# snes_hook.net
KiCad netlist of a schematic drawn in Altium Designer
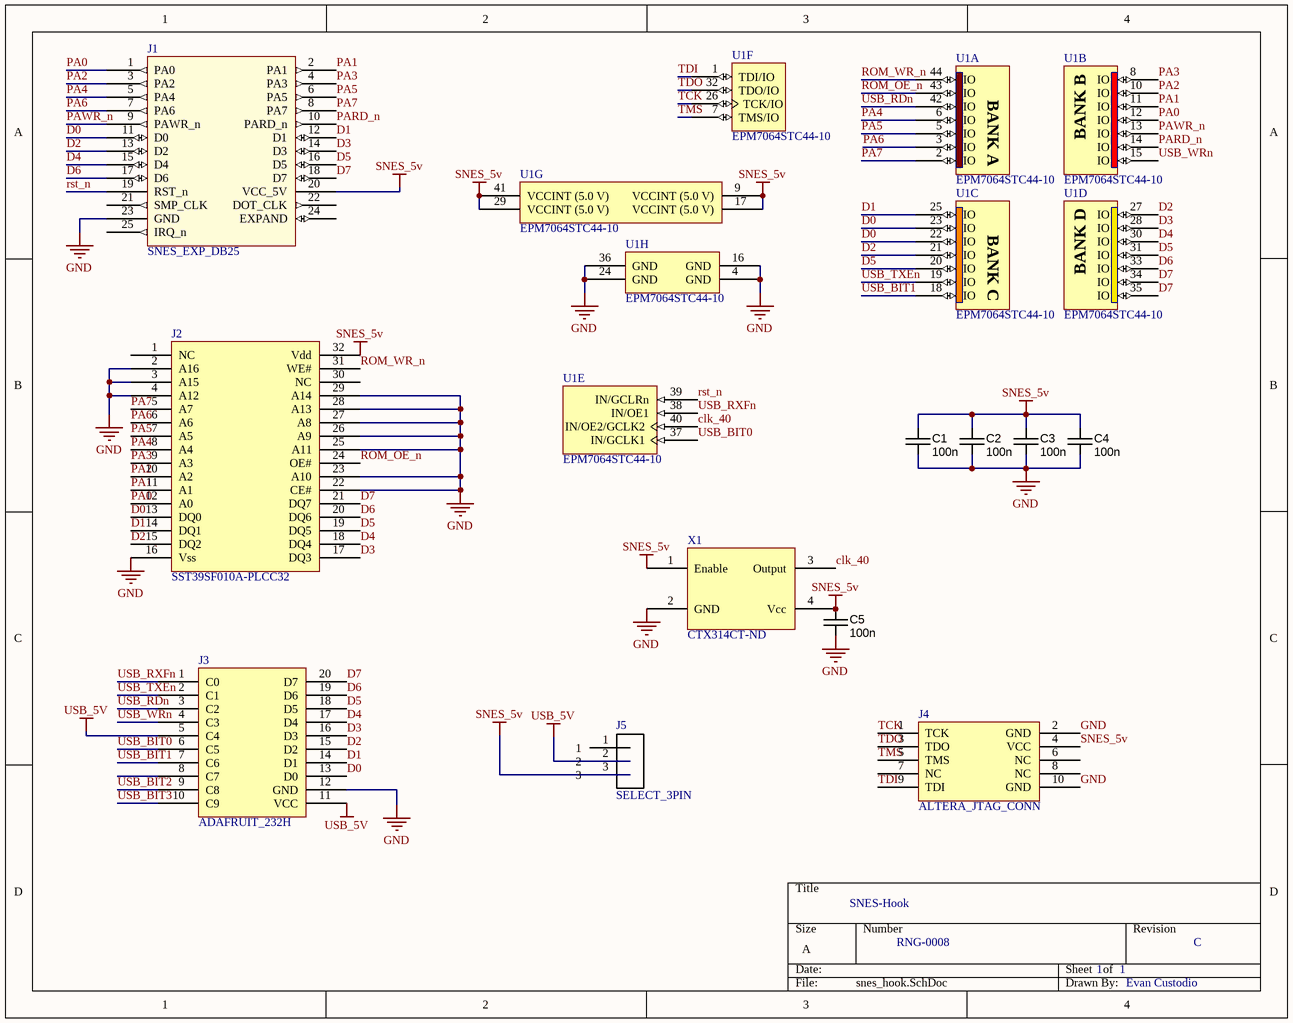
[diagram p0: snes_hook.SchDoc]

(export (version "E")
  (design (tool "Eeschema 10.0.6"))
  (components
    (comp (ref "C1")
      (value "100n")
      (footprint "CAPC1608X90N")
      (description "Capacitor SMD Cer 100nF 10% 50V X7R 0603")
      (fields (field (name "TOLERANCE") "±10%") (field (name "Comment") "approved sub OK"))
      (libsource (lib "snes_hook_parts") (part "CAPC_100n_0603_X7R_50V_10%"))
    )
    (comp (ref "C2")
      (value "100n")
      (footprint "CAPC1608X90N")
      (description "Capacitor SMD Cer 100nF 10% 50V X7R 0603")
      (fields (field (name "TOLERANCE") "±10%") (field (name "Comment") "approved sub OK"))
      (libsource (lib "snes_hook_parts") (part "CAPC_100n_0603_X7R_50V_10%"))
    )
    (comp (ref "C3")
      (value "100n")
      (footprint "CAPC1608X90N")
      (description "Capacitor SMD Cer 100nF 10% 50V X7R 0603")
      (fields (field (name "TOLERANCE") "±10%") (field (name "Comment") "approved sub OK"))
      (libsource (lib "snes_hook_parts") (part "CAPC_100n_0603_X7R_50V_10%"))
    )
    (comp (ref "C4")
      (value "100n")
      (footprint "CAPC1608X90N")
      (description "Capacitor SMD Cer 100nF 10% 50V X7R 0603")
      (fields (field (name "TOLERANCE") "±10%") (field (name "Comment") "approved sub OK"))
      (libsource (lib "snes_hook_parts") (part "CAPC_100n_0603_X7R_50V_10%"))
    )
    (comp (ref "C5")
      (value "100n")
      (footprint "CAPC1608X90N")
      (description "Capacitor SMD Cer 100nF 10% 50V X7R 0603")
      (fields (field (name "TOLERANCE") "±10%") (field (name "Comment") "approved sub OK"))
      (libsource (lib "snes_hook_parts") (part "CAPC_100n_0603_X7R_50V_10%"))
    )
    (comp (ref "J1")
      (value "SNES_EXP_DB25")
      (footprint "DB-25_RA_MPLUG")
      (libsource (lib "snes_hook_parts") (part "SNES_EXP_DB25"))
    )
    (comp (ref "J2")
      (value "SST39SF010A-PLCC32")
      (footprint "PLCC_SOCKET_7x9_32P")
      (libsource (lib "snes_hook_parts") (part "SST39SF010A-PLCC32"))
    )
    (comp (ref "J3")
      (value "ADAFRUIT_232H")
      (footprint "ADAFRUIT_232H")
      (libsource (lib "snes_hook_parts") (part "ADAFRUIT_232H"))
    )
    (comp (ref "J4")
      (value "ALTERA_JTAG_CONN")
      (footprint "JTAG_CONN")
      (libsource (lib "snes_hook_parts") (part "ALTERA_JTAG_CONN"))
    )
    (comp (ref "J5")
      (value "SELECT_3PIN")
      (footprint "HEADER_3PIN")
      (libsource (lib "snes_hook_parts") (part "SELECT_3PIN"))
    )
    (comp (ref "U1")
      (value "EPM7064STC44-10")
      (footprint "TQFP44_L")
      (fields (field (name "PUBLISHER") "Altium Limited"))
      (libsource (lib "snes_hook_parts") (part "EPM7064STC44-10"))
    )
    (comp (ref "X1")
      (value "CTX314CT-ND")
      (footprint "OSCILLATOR_7x5")
      (description "40 MHz 5v Oscillator")
      (fields
        (field (name "MANUFACTURER") "CTS-Frequency Controls")
        (field (name "MANUFACTURER PART NUMBER") "CB3-3I-40M0000")
      )
      (libsource (lib "snes_hook_parts") (part "CTX314CT-ND_40MHz"))
    )
  )
  (nets
    (net (code "1") (name "/D0") (class "Default")
      (node (ref "J1") (pin "11") (pinfunction "D0_11") (pintype "bidirectional"))
      (node (ref "J2") (pin "13") (pinfunction "DQ0_13") (pintype "passive"))
      (node (ref "J3") (pin "13") (pinfunction "D0_13") (pintype "passive"))
      (node (ref "U1") (pin "22") (pinfunction "IO_22") (pintype "bidirectional"))
      (node (ref "U1") (pin "23") (pinfunction "IO_23") (pintype "bidirectional"))
    )
    (net (code "2") (name "/D1") (class "Default")
      (node (ref "J1") (pin "12") (pinfunction "D1_12") (pintype "bidirectional"))
      (node (ref "J2") (pin "14") (pinfunction "DQ1_14") (pintype "passive"))
      (node (ref "J3") (pin "14") (pinfunction "D1_14") (pintype "passive"))
      (node (ref "U1") (pin "25") (pinfunction "IO_25") (pintype "bidirectional"))
    )
    (net (code "3") (name "/D2") (class "Default")
      (node (ref "J1") (pin "13") (pinfunction "D2_13") (pintype "bidirectional"))
      (node (ref "J2") (pin "15") (pinfunction "DQ2_15") (pintype "passive"))
      (node (ref "J3") (pin "15") (pinfunction "D2_15") (pintype "passive"))
      (node (ref "U1") (pin "21") (pinfunction "IO_21") (pintype "bidirectional"))
      (node (ref "U1") (pin "27") (pinfunction "IO_27") (pintype "bidirectional"))
    )
    (net (code "4") (name "/D3") (class "Default")
      (node (ref "J1") (pin "14") (pinfunction "D3_14") (pintype "bidirectional"))
      (node (ref "J2") (pin "17") (pinfunction "DQ3_17") (pintype "passive"))
      (node (ref "J3") (pin "16") (pinfunction "D3_16") (pintype "passive"))
      (node (ref "U1") (pin "28") (pinfunction "IO_28") (pintype "bidirectional"))
    )
    (net (code "5") (name "/D4") (class "Default")
      (node (ref "J1") (pin "15") (pinfunction "D4_15") (pintype "bidirectional"))
      (node (ref "J2") (pin "18") (pinfunction "DQ4_18") (pintype "passive"))
      (node (ref "J3") (pin "17") (pinfunction "D4_17") (pintype "passive"))
      (node (ref "U1") (pin "30") (pinfunction "IO_30") (pintype "bidirectional"))
    )
    (net (code "6") (name "/D5") (class "Default")
      (node (ref "J1") (pin "16") (pinfunction "D5_16") (pintype "bidirectional"))
      (node (ref "J2") (pin "19") (pinfunction "DQ5_19") (pintype "passive"))
      (node (ref "J3") (pin "18") (pinfunction "D5_18") (pintype "passive"))
      (node (ref "U1") (pin "20") (pinfunction "IO_20") (pintype "bidirectional"))
      (node (ref "U1") (pin "31") (pinfunction "IO_31") (pintype "bidirectional"))
    )
    (net (code "7") (name "/D6") (class "Default")
      (node (ref "J1") (pin "17") (pinfunction "D6_17") (pintype "bidirectional"))
      (node (ref "J2") (pin "20") (pinfunction "DQ6_20") (pintype "passive"))
      (node (ref "J3") (pin "19") (pinfunction "D6_19") (pintype "passive"))
      (node (ref "U1") (pin "33") (pinfunction "IO_33") (pintype "bidirectional"))
    )
    (net (code "8") (name "/D7") (class "Default")
      (node (ref "J1") (pin "18") (pinfunction "D7_18") (pintype "bidirectional"))
      (node (ref "J2") (pin "21") (pinfunction "DQ7_21") (pintype "passive"))
      (node (ref "J3") (pin "20") (pinfunction "D7_20") (pintype "passive"))
      (node (ref "U1") (pin "34") (pinfunction "IO_34") (pintype "bidirectional"))
      (node (ref "U1") (pin "35") (pinfunction "IO_35") (pintype "bidirectional"))
    )
    (net (code "9") (name "/PA0") (class "Default")
      (node (ref "J1") (pin "1") (pinfunction "PA0_1") (pintype "output"))
      (node (ref "J2") (pin "12") (pinfunction "A0_12") (pintype "passive"))
      (node (ref "U1") (pin "12") (pinfunction "IO_12") (pintype "bidirectional"))
    )
    (net (code "10") (name "/PA1") (class "Default")
      (node (ref "J1") (pin "2") (pinfunction "PA1_2") (pintype "output"))
      (node (ref "J2") (pin "11") (pinfunction "A1_11") (pintype "passive"))
      (node (ref "U1") (pin "11") (pinfunction "IO_11") (pintype "bidirectional"))
    )
    (net (code "11") (name "/PA2") (class "Default")
      (node (ref "J1") (pin "3") (pinfunction "PA2_3") (pintype "output"))
      (node (ref "J2") (pin "10") (pinfunction "A2_10") (pintype "passive"))
      (node (ref "U1") (pin "10") (pinfunction "IO_10") (pintype "bidirectional"))
    )
    (net (code "12") (name "/PA3") (class "Default")
      (node (ref "J1") (pin "4") (pinfunction "PA3_4") (pintype "output"))
      (node (ref "J2") (pin "9") (pinfunction "A3_9") (pintype "passive"))
      (node (ref "U1") (pin "8") (pinfunction "IO_8") (pintype "bidirectional"))
    )
    (net (code "13") (name "/PA4") (class "Default")
      (node (ref "J1") (pin "5") (pinfunction "PA4_5") (pintype "output"))
      (node (ref "J2") (pin "8") (pinfunction "A4_8") (pintype "passive"))
      (node (ref "U1") (pin "6") (pinfunction "IO_6") (pintype "bidirectional"))
    )
    (net (code "14") (name "/PA5") (class "Default")
      (node (ref "J1") (pin "6") (pinfunction "PA5_6") (pintype "output"))
      (node (ref "J2") (pin "7") (pinfunction "A5_7") (pintype "passive"))
      (node (ref "U1") (pin "5") (pinfunction "IO_5") (pintype "bidirectional"))
    )
    (net (code "15") (name "/PA6") (class "Default")
      (node (ref "J1") (pin "7") (pinfunction "PA6_7") (pintype "output"))
      (node (ref "J2") (pin "6") (pinfunction "A6_6") (pintype "passive"))
      (node (ref "U1") (pin "3") (pinfunction "IO_3") (pintype "bidirectional"))
    )
    (net (code "16") (name "/PA7") (class "Default")
      (node (ref "J1") (pin "8") (pinfunction "PA7_8") (pintype "output"))
      (node (ref "J2") (pin "5") (pinfunction "A7_5") (pintype "passive"))
      (node (ref "U1") (pin "2") (pinfunction "IO_2") (pintype "bidirectional"))
    )
    (net (code "17") (name "/PARD_n") (class "Default")
      (node (ref "J1") (pin "10") (pinfunction "PARD_n_10") (pintype "output"))
      (node (ref "U1") (pin "14") (pinfunction "IO_14") (pintype "bidirectional"))
    )
    (net (code "18") (name "/PAWR_n") (class "Default")
      (node (ref "J1") (pin "9") (pinfunction "PAWR_n_9") (pintype "output"))
      (node (ref "U1") (pin "13") (pinfunction "IO_13") (pintype "bidirectional"))
    )
    (net (code "19") (name "/ROM_OE_n") (class "Default")
      (node (ref "J2") (pin "24") (pinfunction "OE#_24") (pintype "passive"))
      (node (ref "U1") (pin "43") (pinfunction "IO_43") (pintype "bidirectional"))
    )
    (net (code "20") (name "/ROM_WR_n") (class "Default")
      (node (ref "J2") (pin "31") (pinfunction "WE#_31") (pintype "passive"))
      (node (ref "U1") (pin "44") (pinfunction "IO_44") (pintype "bidirectional"))
    )
    (net (code "21") (name "/TCK") (class "Default")
      (node (ref "J4") (pin "1") (pinfunction "TCK_1") (pintype "passive"))
      (node (ref "U1") (pin "26") (pinfunction "TCK/IO_26") (pintype "bidirectional"))
    )
    (net (code "22") (name "/TDI") (class "Default")
      (node (ref "J4") (pin "9") (pinfunction "TDI_9") (pintype "passive"))
      (node (ref "U1") (pin "1") (pinfunction "TDI/IO_1") (pintype "bidirectional"))
    )
    (net (code "23") (name "/TDO") (class "Default")
      (node (ref "J4") (pin "3") (pinfunction "TDO_3") (pintype "passive"))
      (node (ref "U1") (pin "32") (pinfunction "TDO/IO_32") (pintype "bidirectional"))
    )
    (net (code "24") (name "/TMS") (class "Default")
      (node (ref "J4") (pin "5") (pinfunction "TMS_5") (pintype "passive"))
      (node (ref "U1") (pin "7") (pinfunction "TMS/IO_7") (pintype "bidirectional"))
    )
    (net (code "25") (name "/USB_BIT0") (class "Default")
      (node (ref "J3") (pin "6") (pinfunction "C5_6") (pintype "passive"))
      (node (ref "U1") (pin "37") (pinfunction "IN/GCLK1_37") (pintype "input"))
    )
    (net (code "26") (name "/USB_BIT1") (class "Default")
      (node (ref "J3") (pin "7") (pinfunction "C6_7") (pintype "passive"))
      (node (ref "U1") (pin "18") (pinfunction "IO_18") (pintype "bidirectional"))
    )
    (net (code "27") (name "/USB_BIT2") (class "Default")
      (node (ref "J3") (pin "9") (pinfunction "C8_9") (pintype "passive"))
    )
    (net (code "28") (name "/USB_BIT3") (class "Default")
      (node (ref "J3") (pin "10") (pinfunction "C9_10") (pintype "passive"))
    )
    (net (code "29") (name "/USB_RDn") (class "Default")
      (node (ref "J3") (pin "3") (pinfunction "C2_3") (pintype "passive"))
      (node (ref "U1") (pin "42") (pinfunction "IO_42") (pintype "bidirectional"))
    )
    (net (code "30") (name "/USB_RXFn") (class "Default")
      (node (ref "J3") (pin "1") (pinfunction "C0_1") (pintype "passive"))
      (node (ref "U1") (pin "38") (pinfunction "IN/OE1_38") (pintype "input"))
    )
    (net (code "31") (name "/USB_TXEn") (class "Default")
      (node (ref "J3") (pin "2") (pinfunction "C1_2") (pintype "passive"))
      (node (ref "U1") (pin "19") (pinfunction "IO_19") (pintype "bidirectional"))
    )
    (net (code "32") (name "/USB_WRn") (class "Default")
      (node (ref "J3") (pin "4") (pinfunction "C3_4") (pintype "passive"))
      (node (ref "U1") (pin "15") (pinfunction "IO_15") (pintype "bidirectional"))
    )
    (net (code "33") (name "/clk_40") (class "Default")
      (node (ref "U1") (pin "40") (pinfunction "IN/OE2/GCLK2_40") (pintype "input"))
      (node (ref "X1") (pin "3") (pinfunction "Output_3") (pintype "passive"))
    )
    (net (code "34") (name "/rst_n") (class "Default")
      (node (ref "J1") (pin "19") (pinfunction "RST_n_19") (pintype "passive"))
      (node (ref "U1") (pin "39") (pinfunction "IN/GCLRn_39") (pintype "input"))
    )
    (net (code "35") (name "GND") (class "Default")
      (node (ref "C1") (pin "2") (pintype "passive"))
      (node (ref "C2") (pin "2") (pintype "passive"))
      (node (ref "C3") (pin "2") (pintype "passive"))
      (node (ref "C4") (pin "2") (pintype "passive"))
      (node (ref "C5") (pin "2") (pintype "passive"))
      (node (ref "J1") (pin "23") (pinfunction "GND_23") (pintype "passive"))
      (node (ref "J2") (pin "16") (pinfunction "Vss_16") (pintype "passive"))
      (node (ref "J2") (pin "2") (pinfunction "A16_2") (pintype "passive"))
      (node (ref "J2") (pin "22") (pinfunction "CE#_22") (pintype "passive"))
      (node (ref "J2") (pin "23") (pinfunction "A10_23") (pintype "passive"))
      (node (ref "J2") (pin "25") (pinfunction "A11_25") (pintype "passive"))
      (node (ref "J2") (pin "26") (pinfunction "A9_26") (pintype "passive"))
      (node (ref "J2") (pin "27") (pinfunction "A8_27") (pintype "passive"))
      (node (ref "J2") (pin "28") (pinfunction "A13_28") (pintype "passive"))
      (node (ref "J2") (pin "29") (pinfunction "A14_29") (pintype "passive"))
      (node (ref "J2") (pin "3") (pinfunction "A15_3") (pintype "passive"))
      (node (ref "J2") (pin "4") (pinfunction "A12_4") (pintype "passive"))
      (node (ref "J3") (pin "12") (pinfunction "GND_12") (pintype "passive"))
      (node (ref "J4") (pin "10") (pinfunction "GND_10") (pintype "passive"))
      (node (ref "J4") (pin "2") (pinfunction "GND_2") (pintype "passive"))
      (node (ref "U1") (pin "16") (pinfunction "GND_16") (pintype "power_in"))
      (node (ref "U1") (pin "24") (pinfunction "GND_24") (pintype "power_in"))
      (node (ref "U1") (pin "36") (pinfunction "GND_36") (pintype "power_in"))
      (node (ref "U1") (pin "4") (pinfunction "GND_4") (pintype "power_in"))
      (node (ref "X1") (pin "2") (pinfunction "GND_2") (pintype "passive"))
    )
    (net (code "36") (name "SNES_5v") (class "Default")
      (node (ref "C1") (pin "1") (pintype "passive"))
      (node (ref "C2") (pin "1") (pintype "passive"))
      (node (ref "C3") (pin "1") (pintype "passive"))
      (node (ref "C4") (pin "1") (pintype "passive"))
      (node (ref "C5") (pin "1") (pintype "passive"))
      (node (ref "J1") (pin "20") (pinfunction "VCC_5V_20") (pintype "passive"))
      (node (ref "J2") (pin "32") (pinfunction "Vdd_32") (pintype "passive"))
      (node (ref "J4") (pin "4") (pinfunction "VCC_4") (pintype "passive"))
      (node (ref "J5") (pin "3") (pinfunction "3_3") (pintype "passive"))
      (node (ref "U1") (pin "17") (pinfunction "VCCINT_(5.0_V)_17") (pintype "power_in"))
      (node (ref "U1") (pin "29") (pinfunction "VCCINT_(5.0_V)_29") (pintype "power_in"))
      (node (ref "U1") (pin "41") (pinfunction "VCCINT_(5.0_V)_41") (pintype "power_in"))
      (node (ref "U1") (pin "9") (pinfunction "VCCINT_(5.0_V)_9") (pintype "power_in"))
      (node (ref "X1") (pin "1") (pinfunction "Enable_1") (pintype "passive"))
      (node (ref "X1") (pin "4") (pinfunction "Vcc_4") (pintype "passive"))
    )
    (net (code "37") (name "USB_5V") (class "Default")
      (node (ref "J3") (pin "11") (pinfunction "VCC_11") (pintype "passive"))
      (node (ref "J3") (pin "5") (pinfunction "C4_5") (pintype "passive"))
      (node (ref "J5") (pin "2") (pinfunction "2_2") (pintype "passive"))
    )
    (net (code "38") (name "unconnected-(J1-DOT_CLK-Pad22)") (class "Default")
      (node (ref "J1") (pin "22") (pinfunction "DOT_CLK_22") (pintype "output"))
    )
    (net (code "39") (name "unconnected-(J1-EXPAND-Pad24)") (class "Default")
      (node (ref "J1") (pin "24") (pinfunction "EXPAND_24") (pintype "bidirectional"))
    )
    (net (code "40") (name "unconnected-(J1-IRQ_n-Pad25)") (class "Default")
      (node (ref "J1") (pin "25") (pinfunction "IRQ_n_25") (pintype "output"))
    )
    (net (code "41") (name "unconnected-(J1-SMP_CLK-Pad21)") (class "Default")
      (node (ref "J1") (pin "21") (pinfunction "SMP_CLK_21") (pintype "output"))
    )
    (net (code "42") (name "unconnected-(J2-NC-Pad1)") (class "Default")
      (node (ref "J2") (pin "1") (pinfunction "NC_1") (pintype "passive"))
    )
    (net (code "43") (name "unconnected-(J2-NC-Pad30)") (class "Default")
      (node (ref "J2") (pin "30") (pinfunction "NC_30") (pintype "passive"))
    )
    (net (code "44") (name "unconnected-(J3-C7-Pad8)") (class "Default")
      (node (ref "J3") (pin "8") (pinfunction "C7_8") (pintype "passive"))
    )
    (net (code "45") (name "unconnected-(J4-NC-Pad6)") (class "Default")
      (node (ref "J4") (pin "6") (pinfunction "NC_6") (pintype "passive"))
    )
    (net (code "46") (name "unconnected-(J4-NC-Pad7)") (class "Default")
      (node (ref "J4") (pin "7") (pinfunction "NC_7") (pintype "passive"))
    )
    (net (code "47") (name "unconnected-(J4-NC-Pad8)") (class "Default")
      (node (ref "J4") (pin "8") (pinfunction "NC_8") (pintype "passive"))
    )
    (net (code "48") (name "unconnected-(J5-Pad1)") (class "Default")
      (node (ref "J5") (pin "1") (pinfunction "1_1") (pintype "passive"))
    )
  )
)
